# MAGI_sMegaCore.net
KiCad netlist of a schematic drawn in Altium Designer
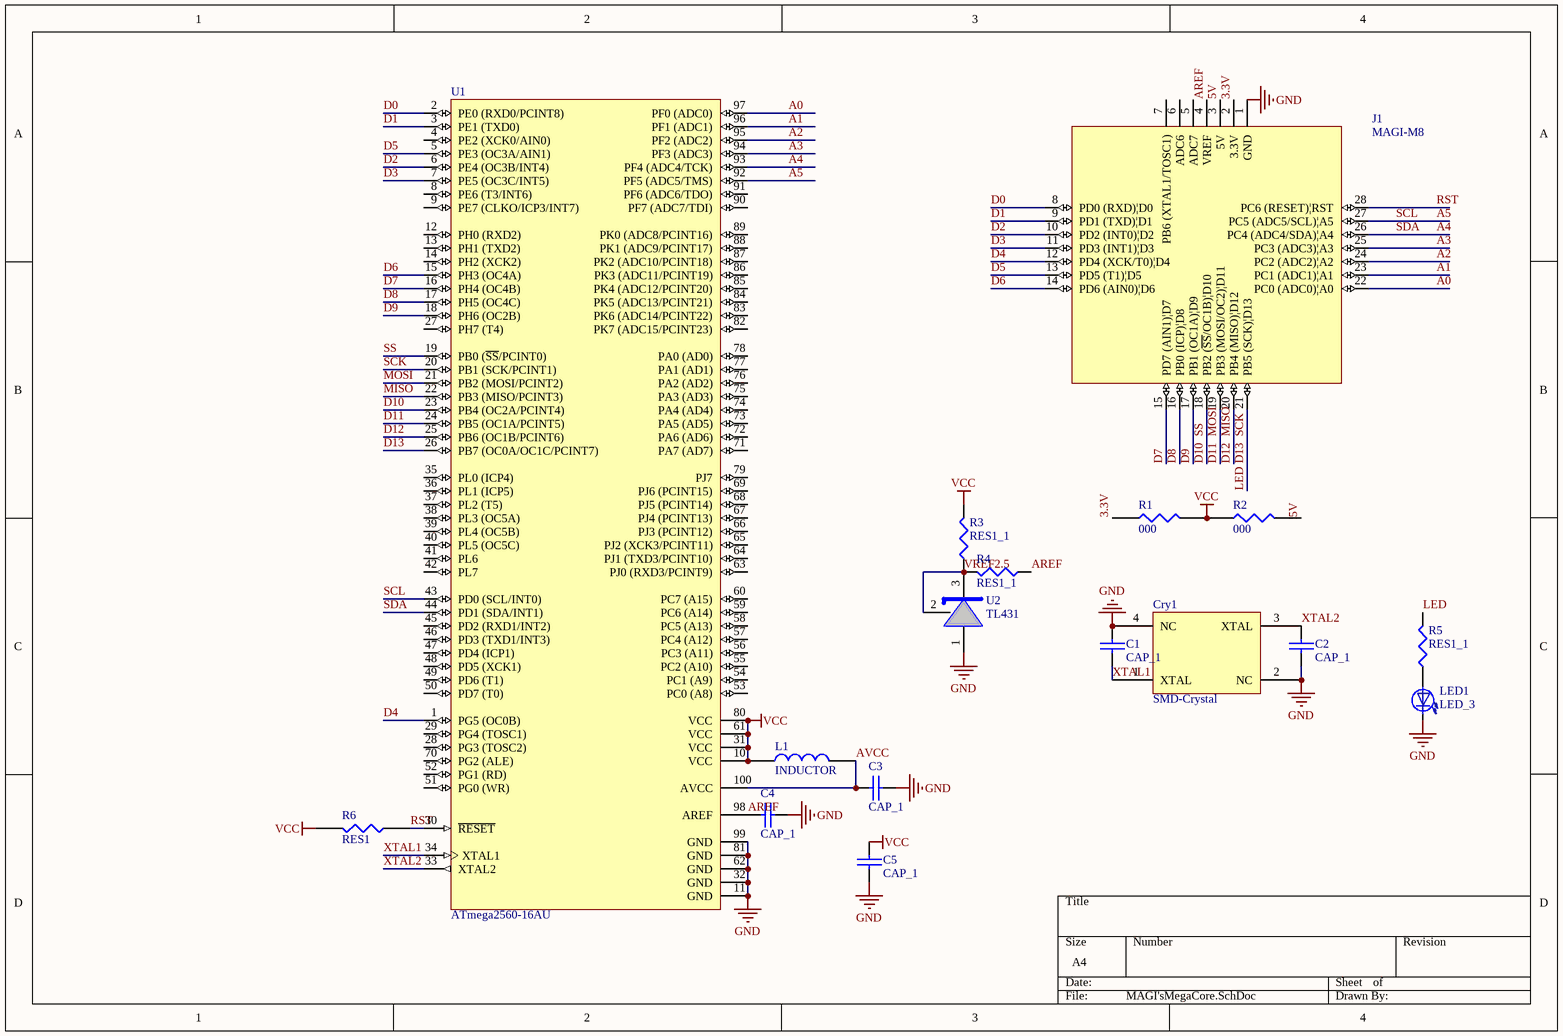
[diagram p0: MAGI'sMegaCore.SchDoc]

(export (version "E")
  (design (tool "Eeschema 10.0.6"))
  (components
    (comp (ref "C1")
      (value "CAP_1")
      (footprint "1608[0603]")
      (description "Capacitor")
      (libsource (lib "电容器") (part "CAP_1"))
    )
    (comp (ref "C2")
      (value "CAP_1")
      (footprint "1608[0603]")
      (description "Capacitor")
      (libsource (lib "电容器") (part "CAP_1"))
    )
    (comp (ref "C3")
      (value "CAP_1")
      (footprint "6-0805_N")
      (description "Capacitor")
      (libsource (lib "电容器") (part "CAP_1"))
    )
    (comp (ref "C4")
      (value "CAP_1")
      (footprint "6-0805_N")
      (description "Capacitor")
      (libsource (lib "电容器") (part "CAP_1"))
    )
    (comp (ref "C5")
      (value "CAP_1")
      (footprint "C1210_N")
      (description "Capacitor")
      (libsource (lib "电容器") (part "CAP_1"))
    )
    (comp (ref "Cry1") (value "SMD-Crystal") (footprint "3225") (libsource (lib "XTAL") (part "Crystal")))
    (comp (ref "J1") (value "MAGI-M8") (footprint "MAGI-M8") (libsource (lib "MAGI-M8") (part "MAGI-M8")))
    (comp (ref "L1") (value "INDUCTOR") (footprint "6-0805_n") (libsource (lib "汇总") (part "INDUCTOR")))
    (comp (ref "LED1") (value "LED_3") (footprint "6-0805_N") (libsource (lib "二极管") (part "LED_3")))
    (comp (ref "R1") (value "000") (footprint "6-0805_N") (libsource (lib "电阻器") (part "RES1")))
    (comp (ref "R2") (value "000") (footprint "6-0805_N") (libsource (lib "电阻器") (part "RES1")))
    (comp (ref "R3") (value "RES1_1") (footprint "6-0805_N") (libsource (lib "电阻器") (part "RES1_1")))
    (comp (ref "R4") (value "RES1_1") (footprint "6-0805_N") (libsource (lib "电阻器") (part "RES1_1")))
    (comp (ref "R5") (value "RES1_1") (footprint "6-0805_N") (libsource (lib "电阻器") (part "RES1_1")))
    (comp (ref "R6") (value "RES1") (footprint "6-0805_N") (libsource (lib "电阻器") (part "RES1")))
    (comp (ref "U1")
      (value "ATmega2560-16AU")
      (footprint "100A_N")
      (fields (field (name "PUBLISHER") "Altium Limited"))
      (libsource (lib "Atmel Microcontroller 8-Bit megaAVR") (part "ATmega2560-16AU"))
    )
    (comp (ref "U2") (value "TL431") (footprint "SOT23_N") (libsource (lib "汇总") (part "TL431")))
  )
  (nets
    (net (code "1") (name "/3.3V") (class "Default")
      (node (ref "J1") (pin "2") (pinfunction "3.3V_2") (pintype "power_in"))
      (node (ref "R1") (pin "1") (pinfunction "1_1") (pintype "passive"))
    )
    (net (code "2") (name "/5V") (class "Default")
      (node (ref "J1") (pin "3") (pinfunction "5V_3") (pintype "power_in"))
      (node (ref "R2") (pin "2") (pinfunction "2_2") (pintype "passive"))
    )
    (net (code "3") (name "/A0") (class "Default")
      (node (ref "J1") (pin "22") (pinfunction "PC0_(ADC0)¦A0_22") (pintype "bidirectional"))
      (node (ref "U1") (pin "97") (pinfunction "PF0_(ADC0)_97") (pintype "bidirectional"))
    )
    (net (code "4") (name "/A1") (class "Default")
      (node (ref "J1") (pin "23") (pinfunction "PC1_(ADC1)¦A1_23") (pintype "bidirectional"))
      (node (ref "U1") (pin "96") (pinfunction "PF1_(ADC1)_96") (pintype "bidirectional"))
    )
    (net (code "5") (name "/A2") (class "Default")
      (node (ref "J1") (pin "24") (pinfunction "PC2_(ADC2)¦A2_24") (pintype "bidirectional"))
      (node (ref "U1") (pin "95") (pinfunction "PF2_(ADC2)_95") (pintype "bidirectional"))
    )
    (net (code "6") (name "/A3") (class "Default")
      (node (ref "J1") (pin "25") (pinfunction "PC3_(ADC3)¦A3_25") (pintype "bidirectional"))
      (node (ref "U1") (pin "94") (pinfunction "PF3_(ADC3)_94") (pintype "bidirectional"))
    )
    (net (code "7") (name "/A4") (class "Default")
      (node (ref "J1") (pin "26") (pinfunction "PC4_(ADC4/SDA)¦A4_26") (pintype "bidirectional"))
      (node (ref "U1") (pin "44") (pinfunction "PD1_(SDA/INT1)_44") (pintype "bidirectional"))
      (node (ref "U1") (pin "93") (pinfunction "PF4_(ADC4/TCK)_93") (pintype "bidirectional"))
    )
    (net (code "8") (name "/A5") (class "Default")
      (node (ref "J1") (pin "27") (pinfunction "PC5_(ADC5/SCL)¦A5_27") (pintype "bidirectional"))
      (node (ref "U1") (pin "43") (pinfunction "PD0_(SCL/INT0)_43") (pintype "bidirectional"))
      (node (ref "U1") (pin "92") (pinfunction "PF5_(ADC5/TMS)_92") (pintype "bidirectional"))
    )
    (net (code "9") (name "/AREF") (class "Default")
      (node (ref "C4") (pin "2") (pinfunction "2_2") (pintype "passive"))
      (node (ref "J1") (pin "4") (pinfunction "VREF_4") (pintype "passive"))
      (node (ref "R4") (pin "1") (pinfunction "1_1") (pintype "passive"))
      (node (ref "U1") (pin "98") (pinfunction "AREF_98") (pintype "power_in"))
    )
    (net (code "10") (name "/AVCC") (class "Default")
      (node (ref "C3") (pin "2") (pinfunction "2_2") (pintype "passive"))
      (node (ref "L1") (pin "1") (pinfunction "1_1") (pintype "passive"))
      (node (ref "U1") (pin "100") (pinfunction "AVCC_100") (pintype "power_in"))
    )
    (net (code "11") (name "/D0") (class "Default")
      (node (ref "J1") (pin "8") (pinfunction "PD0_(RXD)¦D0_8") (pintype "bidirectional"))
      (node (ref "U1") (pin "2") (pinfunction "PE0_(RXD0/PCINT8)_2") (pintype "bidirectional"))
    )
    (net (code "12") (name "/D1") (class "Default")
      (node (ref "J1") (pin "9") (pinfunction "PD1_(TXD)¦D1_9") (pintype "bidirectional"))
      (node (ref "U1") (pin "3") (pinfunction "PE1_(TXD0)_3") (pintype "bidirectional"))
    )
    (net (code "13") (name "/D2") (class "Default")
      (node (ref "J1") (pin "10") (pinfunction "PD2_(INT0)¦D2_10") (pintype "bidirectional"))
      (node (ref "U1") (pin "6") (pinfunction "PE4_(OC3B/INT4)_6") (pintype "bidirectional"))
    )
    (net (code "14") (name "/D3") (class "Default")
      (node (ref "J1") (pin "11") (pinfunction "PD3_(INT1)¦D3_11") (pintype "bidirectional"))
      (node (ref "U1") (pin "7") (pinfunction "PE5_(OC3C/INT5)_7") (pintype "bidirectional"))
    )
    (net (code "15") (name "/D4") (class "Default")
      (node (ref "J1") (pin "12") (pinfunction "PD4_(XCK/T0)¦D4_12") (pintype "bidirectional"))
      (node (ref "U1") (pin "1") (pinfunction "PG5_(OC0B)_1") (pintype "bidirectional"))
    )
    (net (code "16") (name "/D5") (class "Default")
      (node (ref "J1") (pin "13") (pinfunction "PD5_(T1)¦D5_13") (pintype "bidirectional"))
      (node (ref "U1") (pin "5") (pinfunction "PE3_(OC3A/AIN1)_5") (pintype "bidirectional"))
    )
    (net (code "17") (name "/D6") (class "Default")
      (node (ref "J1") (pin "14") (pinfunction "PD6_(AIN0)¦D6_14") (pintype "bidirectional"))
      (node (ref "U1") (pin "15") (pinfunction "PH3_(OC4A)_15") (pintype "bidirectional"))
    )
    (net (code "18") (name "/D7") (class "Default")
      (node (ref "J1") (pin "15") (pinfunction "PD7_(AIN1)¦D7_15") (pintype "bidirectional"))
      (node (ref "U1") (pin "16") (pinfunction "PH4_(OC4B)_16") (pintype "bidirectional"))
    )
    (net (code "19") (name "/D8") (class "Default")
      (node (ref "J1") (pin "16") (pinfunction "PB0_(ICP)¦D8_16") (pintype "bidirectional"))
      (node (ref "U1") (pin "17") (pinfunction "PH5_(OC4C)_17") (pintype "bidirectional"))
    )
    (net (code "20") (name "/D9") (class "Default")
      (node (ref "J1") (pin "17") (pinfunction "PB1_(OC1A)¦D9_17") (pintype "bidirectional"))
      (node (ref "U1") (pin "18") (pinfunction "PH6_(OC2B)_18") (pintype "bidirectional"))
    )
    (net (code "21") (name "/D10") (class "Default")
      (node (ref "J1") (pin "18") (pinfunction "PB2_(~{SS}/OC1B)¦D10_18") (pintype "bidirectional"))
      (node (ref "U1") (pin "19") (pinfunction "PB0_(~{SS}/PCINT0)_19") (pintype "bidirectional"))
      (node (ref "U1") (pin "23") (pinfunction "PB4_(OC2A/PCINT4)_23") (pintype "bidirectional"))
    )
    (net (code "22") (name "/D11") (class "Default")
      (node (ref "J1") (pin "19") (pinfunction "PB3_(MOSI/OC2)¦D11_19") (pintype "bidirectional"))
      (node (ref "U1") (pin "21") (pinfunction "PB2_(MOSI/PCINT2)_21") (pintype "bidirectional"))
      (node (ref "U1") (pin "24") (pinfunction "PB5_(OC1A/PCINT5)_24") (pintype "bidirectional"))
    )
    (net (code "23") (name "/D12") (class "Default")
      (node (ref "J1") (pin "20") (pinfunction "PB4_(MISO)¦D12_20") (pintype "bidirectional"))
      (node (ref "U1") (pin "22") (pinfunction "PB3_(MISO/PCINT3)_22") (pintype "bidirectional"))
      (node (ref "U1") (pin "25") (pinfunction "PB6_(OC1B/PCINT6)_25") (pintype "bidirectional"))
    )
    (net (code "24") (name "/D13") (class "Default")
      (node (ref "J1") (pin "21") (pinfunction "PB5_(SCK)¦D13_21") (pintype "bidirectional"))
      (node (ref "R5") (pin "2") (pinfunction "2_2") (pintype "passive"))
      (node (ref "U1") (pin "20") (pinfunction "PB1_(SCK/PCINT1)_20") (pintype "bidirectional"))
      (node (ref "U1") (pin "26") (pinfunction "PB7_(OC0A/OC1C/PCINT7)_26") (pintype "bidirectional"))
    )
    (net (code "25") (name "/RST") (class "Default")
      (node (ref "J1") (pin "28") (pinfunction "PC6_(RESET)¦RST_28") (pintype "bidirectional"))
      (node (ref "R6") (pin "1") (pinfunction "1_1") (pintype "passive"))
      (node (ref "U1") (pin "30") (pinfunction "~{RESET}_30") (pintype "input"))
    )
    (net (code "26") (name "/VREF2.5") (class "Default")
      (node (ref "R3") (pin "1") (pinfunction "1_1") (pintype "passive"))
      (node (ref "R4") (pin "2") (pinfunction "2_2") (pintype "passive"))
      (node (ref "U2") (pin "2") (pinfunction "REF_2") (pintype "passive"))
      (node (ref "U2") (pin "3") (pinfunction "ANODE_3") (pintype "passive"))
    )
    (net (code "27") (name "/XTAL1") (class "Default")
      (node (ref "C1") (pin "1") (pinfunction "1_1") (pintype "passive"))
      (node (ref "Cry1") (pin "1") (pinfunction "XTAL_1") (pintype "passive"))
      (node (ref "U1") (pin "34") (pinfunction "XTAL1_34") (pintype "input"))
    )
    (net (code "28") (name "/XTAL2") (class "Default")
      (node (ref "C2") (pin "2") (pinfunction "2_2") (pintype "passive"))
      (node (ref "Cry1") (pin "3") (pinfunction "XTAL_3") (pintype "passive"))
      (node (ref "U1") (pin "33") (pinfunction "XTAL2_33") (pintype "output"))
    )
    (net (code "29") (name "GND") (class "Default")
      (node (ref "C1") (pin "2") (pinfunction "2_2") (pintype "passive"))
      (node (ref "C2") (pin "1") (pinfunction "1_1") (pintype "passive"))
      (node (ref "C3") (pin "1") (pinfunction "1_1") (pintype "passive"))
      (node (ref "C4") (pin "1") (pinfunction "1_1") (pintype "passive"))
      (node (ref "C5") (pin "1") (pinfunction "1_1") (pintype "passive"))
      (node (ref "Cry1") (pin "2") (pinfunction "NC_2") (pintype "passive"))
      (node (ref "Cry1") (pin "4") (pinfunction "NC_4") (pintype "passive"))
      (node (ref "J1") (pin "1") (pinfunction "GND_1") (pintype "power_in"))
      (node (ref "LED1") (pin "2") (pinfunction "K_2") (pintype "passive"))
      (node (ref "U1") (pin "11") (pinfunction "GND_11") (pintype "power_in"))
      (node (ref "U1") (pin "32") (pinfunction "GND_32") (pintype "power_in"))
      (node (ref "U1") (pin "62") (pinfunction "GND_62") (pintype "power_in"))
      (node (ref "U1") (pin "81") (pinfunction "GND_81") (pintype "power_in"))
      (node (ref "U1") (pin "99") (pinfunction "GND_99") (pintype "power_in"))
      (node (ref "U2") (pin "1") (pinfunction "CATHODE_1") (pintype "passive"))
    )
    (net (code "30") (name "Net-(LED1-A)") (class "Default")
      (node (ref "LED1") (pin "1") (pinfunction "A_1") (pintype "passive"))
      (node (ref "R5") (pin "1") (pinfunction "1_1") (pintype "passive"))
    )
    (net (code "31") (name "VCC") (class "Default")
      (node (ref "C5") (pin "2") (pinfunction "2_2") (pintype "passive"))
      (node (ref "L1") (pin "2") (pinfunction "2_2") (pintype "passive"))
      (node (ref "R1") (pin "2") (pinfunction "2_2") (pintype "passive"))
      (node (ref "R2") (pin "1") (pinfunction "1_1") (pintype "passive"))
      (node (ref "R3") (pin "2") (pinfunction "2_2") (pintype "passive"))
      (node (ref "R6") (pin "2") (pinfunction "2_2") (pintype "passive"))
      (node (ref "U1") (pin "10") (pinfunction "VCC_10") (pintype "power_in"))
      (node (ref "U1") (pin "31") (pinfunction "VCC_31") (pintype "power_in"))
      (node (ref "U1") (pin "61") (pinfunction "VCC_61") (pintype "power_in"))
      (node (ref "U1") (pin "80") (pinfunction "VCC_80") (pintype "power_in"))
    )
    (net (code "32") (name "unconnected-(J1-ADC6-Pad6)") (class "Default")
      (node (ref "J1") (pin "6") (pinfunction "ADC6_6") (pintype "passive"))
    )
    (net (code "33") (name "unconnected-(J1-ADC7-Pad5)") (class "Default")
      (node (ref "J1") (pin "5") (pinfunction "ADC7_5") (pintype "passive"))
    )
    (net (code "34") (name "unconnected-(J1-PB6_(XTAL1{slash}TOSC1)-Pad7)") (class "Default")
      (node (ref "J1") (pin "7") (pinfunction "PB6_(XTAL1/TOSC1)_7") (pintype "passive"))
    )
    (net (code "35") (name "unconnected-(U1-PA0_(AD0)-Pad78)") (class "Default")
      (node (ref "U1") (pin "78") (pinfunction "PA0_(AD0)_78") (pintype "bidirectional"))
    )
    (net (code "36") (name "unconnected-(U1-PA1_(AD1)-Pad77)") (class "Default")
      (node (ref "U1") (pin "77") (pinfunction "PA1_(AD1)_77") (pintype "bidirectional"))
    )
    (net (code "37") (name "unconnected-(U1-PA2_(AD2)-Pad76)") (class "Default")
      (node (ref "U1") (pin "76") (pinfunction "PA2_(AD2)_76") (pintype "bidirectional"))
    )
    (net (code "38") (name "unconnected-(U1-PA3_(AD3)-Pad75)") (class "Default")
      (node (ref "U1") (pin "75") (pinfunction "PA3_(AD3)_75") (pintype "bidirectional"))
    )
    (net (code "39") (name "unconnected-(U1-PA4_(AD4)-Pad74)") (class "Default")
      (node (ref "U1") (pin "74") (pinfunction "PA4_(AD4)_74") (pintype "bidirectional"))
    )
    (net (code "40") (name "unconnected-(U1-PA5_(AD5)-Pad73)") (class "Default")
      (node (ref "U1") (pin "73") (pinfunction "PA5_(AD5)_73") (pintype "bidirectional"))
    )
    (net (code "41") (name "unconnected-(U1-PA6_(AD6)-Pad72)") (class "Default")
      (node (ref "U1") (pin "72") (pinfunction "PA6_(AD6)_72") (pintype "bidirectional"))
    )
    (net (code "42") (name "unconnected-(U1-PA7_(AD7)-Pad71)") (class "Default")
      (node (ref "U1") (pin "71") (pinfunction "PA7_(AD7)_71") (pintype "bidirectional"))
    )
    (net (code "43") (name "unconnected-(U1-PC0_(A8)-Pad53)") (class "Default")
      (node (ref "U1") (pin "53") (pinfunction "PC0_(A8)_53") (pintype "bidirectional"))
    )
    (net (code "44") (name "unconnected-(U1-PC1_(A9)-Pad54)") (class "Default")
      (node (ref "U1") (pin "54") (pinfunction "PC1_(A9)_54") (pintype "bidirectional"))
    )
    (net (code "45") (name "unconnected-(U1-PC2_(A10)-Pad55)") (class "Default")
      (node (ref "U1") (pin "55") (pinfunction "PC2_(A10)_55") (pintype "bidirectional"))
    )
    (net (code "46") (name "unconnected-(U1-PC3_(A11)-Pad56)") (class "Default")
      (node (ref "U1") (pin "56") (pinfunction "PC3_(A11)_56") (pintype "bidirectional"))
    )
    (net (code "47") (name "unconnected-(U1-PC4_(A12)-Pad57)") (class "Default")
      (node (ref "U1") (pin "57") (pinfunction "PC4_(A12)_57") (pintype "bidirectional"))
    )
    (net (code "48") (name "unconnected-(U1-PC5_(A13)-Pad58)") (class "Default")
      (node (ref "U1") (pin "58") (pinfunction "PC5_(A13)_58") (pintype "bidirectional"))
    )
    (net (code "49") (name "unconnected-(U1-PC6_(A14)-Pad59)") (class "Default")
      (node (ref "U1") (pin "59") (pinfunction "PC6_(A14)_59") (pintype "bidirectional"))
    )
    (net (code "50") (name "unconnected-(U1-PC7_(A15)-Pad60)") (class "Default")
      (node (ref "U1") (pin "60") (pinfunction "PC7_(A15)_60") (pintype "bidirectional"))
    )
    (net (code "51") (name "unconnected-(U1-PD2_(RXD1{slash}INT2)-Pad45)") (class "Default")
      (node (ref "U1") (pin "45") (pinfunction "PD2_(RXD1/INT2)_45") (pintype "bidirectional"))
    )
    (net (code "52") (name "unconnected-(U1-PD3_(TXD1{slash}INT3)-Pad46)") (class "Default")
      (node (ref "U1") (pin "46") (pinfunction "PD3_(TXD1/INT3)_46") (pintype "bidirectional"))
    )
    (net (code "53") (name "unconnected-(U1-PD4_(ICP1)-Pad47)") (class "Default")
      (node (ref "U1") (pin "47") (pinfunction "PD4_(ICP1)_47") (pintype "bidirectional"))
    )
    (net (code "54") (name "unconnected-(U1-PD5_(XCK1)-Pad48)") (class "Default")
      (node (ref "U1") (pin "48") (pinfunction "PD5_(XCK1)_48") (pintype "bidirectional"))
    )
    (net (code "55") (name "unconnected-(U1-PD6_(T1)-Pad49)") (class "Default")
      (node (ref "U1") (pin "49") (pinfunction "PD6_(T1)_49") (pintype "bidirectional"))
    )
    (net (code "56") (name "unconnected-(U1-PD7_(T0)-Pad50)") (class "Default")
      (node (ref "U1") (pin "50") (pinfunction "PD7_(T0)_50") (pintype "bidirectional"))
    )
    (net (code "57") (name "unconnected-(U1-PE2_(XCK0{slash}AIN0)-Pad4)") (class "Default")
      (node (ref "U1") (pin "4") (pinfunction "PE2_(XCK0/AIN0)_4") (pintype "bidirectional"))
    )
    (net (code "58") (name "unconnected-(U1-PE6_(T3{slash}INT6)-Pad8)") (class "Default")
      (node (ref "U1") (pin "8") (pinfunction "PE6_(T3/INT6)_8") (pintype "bidirectional"))
    )
    (net (code "59") (name "unconnected-(U1-PE7_(CLKO{slash}ICP3{slash}INT7)-Pad9)") (class "Default")
      (node (ref "U1") (pin "9") (pinfunction "PE7_(CLKO/ICP3/INT7)_9") (pintype "bidirectional"))
    )
    (net (code "60") (name "unconnected-(U1-PF6_(ADC6{slash}TDO)-Pad91)") (class "Default")
      (node (ref "U1") (pin "91") (pinfunction "PF6_(ADC6/TDO)_91") (pintype "bidirectional"))
    )
    (net (code "61") (name "unconnected-(U1-PF7_(ADC7{slash}TDI)-Pad90)") (class "Default")
      (node (ref "U1") (pin "90") (pinfunction "PF7_(ADC7/TDI)_90") (pintype "bidirectional"))
    )
    (net (code "62") (name "unconnected-(U1-PG0_(WR)-Pad51)") (class "Default")
      (node (ref "U1") (pin "51") (pinfunction "PG0_(WR)_51") (pintype "bidirectional"))
    )
    (net (code "63") (name "unconnected-(U1-PG1_(RD)-Pad52)") (class "Default")
      (node (ref "U1") (pin "52") (pinfunction "PG1_(RD)_52") (pintype "bidirectional"))
    )
    (net (code "64") (name "unconnected-(U1-PG2_(ALE)-Pad70)") (class "Default")
      (node (ref "U1") (pin "70") (pinfunction "PG2_(ALE)_70") (pintype "bidirectional"))
    )
    (net (code "65") (name "unconnected-(U1-PG3_(TOSC2)-Pad28)") (class "Default")
      (node (ref "U1") (pin "28") (pinfunction "PG3_(TOSC2)_28") (pintype "bidirectional"))
    )
    (net (code "66") (name "unconnected-(U1-PG4_(TOSC1)-Pad29)") (class "Default")
      (node (ref "U1") (pin "29") (pinfunction "PG4_(TOSC1)_29") (pintype "bidirectional"))
    )
    (net (code "67") (name "unconnected-(U1-PH0_(RXD2)-Pad12)") (class "Default")
      (node (ref "U1") (pin "12") (pinfunction "PH0_(RXD2)_12") (pintype "bidirectional"))
    )
    (net (code "68") (name "unconnected-(U1-PH1_(TXD2)-Pad13)") (class "Default")
      (node (ref "U1") (pin "13") (pinfunction "PH1_(TXD2)_13") (pintype "bidirectional"))
    )
    (net (code "69") (name "unconnected-(U1-PH2_(XCK2)-Pad14)") (class "Default")
      (node (ref "U1") (pin "14") (pinfunction "PH2_(XCK2)_14") (pintype "bidirectional"))
    )
    (net (code "70") (name "unconnected-(U1-PH7_(T4)-Pad27)") (class "Default")
      (node (ref "U1") (pin "27") (pinfunction "PH7_(T4)_27") (pintype "bidirectional"))
    )
    (net (code "71") (name "unconnected-(U1-PJ0_(RXD3{slash}PCINT9)-Pad63)") (class "Default")
      (node (ref "U1") (pin "63") (pinfunction "PJ0_(RXD3/PCINT9)_63") (pintype "bidirectional"))
    )
    (net (code "72") (name "unconnected-(U1-PJ1_(TXD3{slash}PCINT10)-Pad64)") (class "Default")
      (node (ref "U1") (pin "64") (pinfunction "PJ1_(TXD3/PCINT10)_64") (pintype "bidirectional"))
    )
    (net (code "73") (name "unconnected-(U1-PJ2_(XCK3{slash}PCINT11)-Pad65)") (class "Default")
      (node (ref "U1") (pin "65") (pinfunction "PJ2_(XCK3/PCINT11)_65") (pintype "bidirectional"))
    )
    (net (code "74") (name "unconnected-(U1-PJ3_(PCINT12)-Pad66)") (class "Default")
      (node (ref "U1") (pin "66") (pinfunction "PJ3_(PCINT12)_66") (pintype "bidirectional"))
    )
    (net (code "75") (name "unconnected-(U1-PJ4_(PCINT13)-Pad67)") (class "Default")
      (node (ref "U1") (pin "67") (pinfunction "PJ4_(PCINT13)_67") (pintype "bidirectional"))
    )
    (net (code "76") (name "unconnected-(U1-PJ5_(PCINT14)-Pad68)") (class "Default")
      (node (ref "U1") (pin "68") (pinfunction "PJ5_(PCINT14)_68") (pintype "bidirectional"))
    )
    (net (code "77") (name "unconnected-(U1-PJ6_(PCINT15)-Pad69)") (class "Default")
      (node (ref "U1") (pin "69") (pinfunction "PJ6_(PCINT15)_69") (pintype "bidirectional"))
    )
    (net (code "78") (name "unconnected-(U1-PJ7-Pad79)") (class "Default")
      (node (ref "U1") (pin "79") (pinfunction "PJ7_79") (pintype "bidirectional"))
    )
    (net (code "79") (name "unconnected-(U1-PK0_(ADC8{slash}PCINT16)-Pad89)") (class "Default")
      (node (ref "U1") (pin "89") (pinfunction "PK0_(ADC8/PCINT16)_89") (pintype "bidirectional"))
    )
    (net (code "80") (name "unconnected-(U1-PK1_(ADC9{slash}PCINT17)-Pad88)") (class "Default")
      (node (ref "U1") (pin "88") (pinfunction "PK1_(ADC9/PCINT17)_88") (pintype "bidirectional"))
    )
    (net (code "81") (name "unconnected-(U1-PK2_(ADC10{slash}PCINT18)-Pad87)") (class "Default")
      (node (ref "U1") (pin "87") (pinfunction "PK2_(ADC10/PCINT18)_87") (pintype "bidirectional"))
    )
    (net (code "82") (name "unconnected-(U1-PK3_(ADC11{slash}PCINT19)-Pad86)") (class "Default")
      (node (ref "U1") (pin "86") (pinfunction "PK3_(ADC11/PCINT19)_86") (pintype "bidirectional"))
    )
    (net (code "83") (name "unconnected-(U1-PK4_(ADC12{slash}PCINT20)-Pad85)") (class "Default")
      (node (ref "U1") (pin "85") (pinfunction "PK4_(ADC12/PCINT20)_85") (pintype "bidirectional"))
    )
    (net (code "84") (name "unconnected-(U1-PK5_(ADC13{slash}PCINT21)-Pad84)") (class "Default")
      (node (ref "U1") (pin "84") (pinfunction "PK5_(ADC13/PCINT21)_84") (pintype "bidirectional"))
    )
    (net (code "85") (name "unconnected-(U1-PK6_(ADC14{slash}PCINT22)-Pad83)") (class "Default")
      (node (ref "U1") (pin "83") (pinfunction "PK6_(ADC14/PCINT22)_83") (pintype "bidirectional"))
    )
    (net (code "86") (name "unconnected-(U1-PK7_(ADC15{slash}PCINT23)-Pad82)") (class "Default")
      (node (ref "U1") (pin "82") (pinfunction "PK7_(ADC15/PCINT23)_82") (pintype "bidirectional"))
    )
    (net (code "87") (name "unconnected-(U1-PL0_(ICP4)-Pad35)") (class "Default")
      (node (ref "U1") (pin "35") (pinfunction "PL0_(ICP4)_35") (pintype "bidirectional"))
    )
    (net (code "88") (name "unconnected-(U1-PL1_(ICP5)-Pad36)") (class "Default")
      (node (ref "U1") (pin "36") (pinfunction "PL1_(ICP5)_36") (pintype "bidirectional"))
    )
    (net (code "89") (name "unconnected-(U1-PL2_(T5)-Pad37)") (class "Default")
      (node (ref "U1") (pin "37") (pinfunction "PL2_(T5)_37") (pintype "bidirectional"))
    )
    (net (code "90") (name "unconnected-(U1-PL3_(OC5A)-Pad38)") (class "Default")
      (node (ref "U1") (pin "38") (pinfunction "PL3_(OC5A)_38") (pintype "bidirectional"))
    )
    (net (code "91") (name "unconnected-(U1-PL4_(OC5B)-Pad39)") (class "Default")
      (node (ref "U1") (pin "39") (pinfunction "PL4_(OC5B)_39") (pintype "bidirectional"))
    )
    (net (code "92") (name "unconnected-(U1-PL5_(OC5C)-Pad40)") (class "Default")
      (node (ref "U1") (pin "40") (pinfunction "PL5_(OC5C)_40") (pintype "bidirectional"))
    )
    (net (code "93") (name "unconnected-(U1-PL6-Pad41)") (class "Default")
      (node (ref "U1") (pin "41") (pinfunction "PL6_41") (pintype "bidirectional"))
    )
    (net (code "94") (name "unconnected-(U1-PL7-Pad42)") (class "Default")
      (node (ref "U1") (pin "42") (pinfunction "PL7_42") (pintype "bidirectional"))
    )
  )
)
